# BottomBoard.net
KiCad netlist of a schematic drawn in Altium Designer
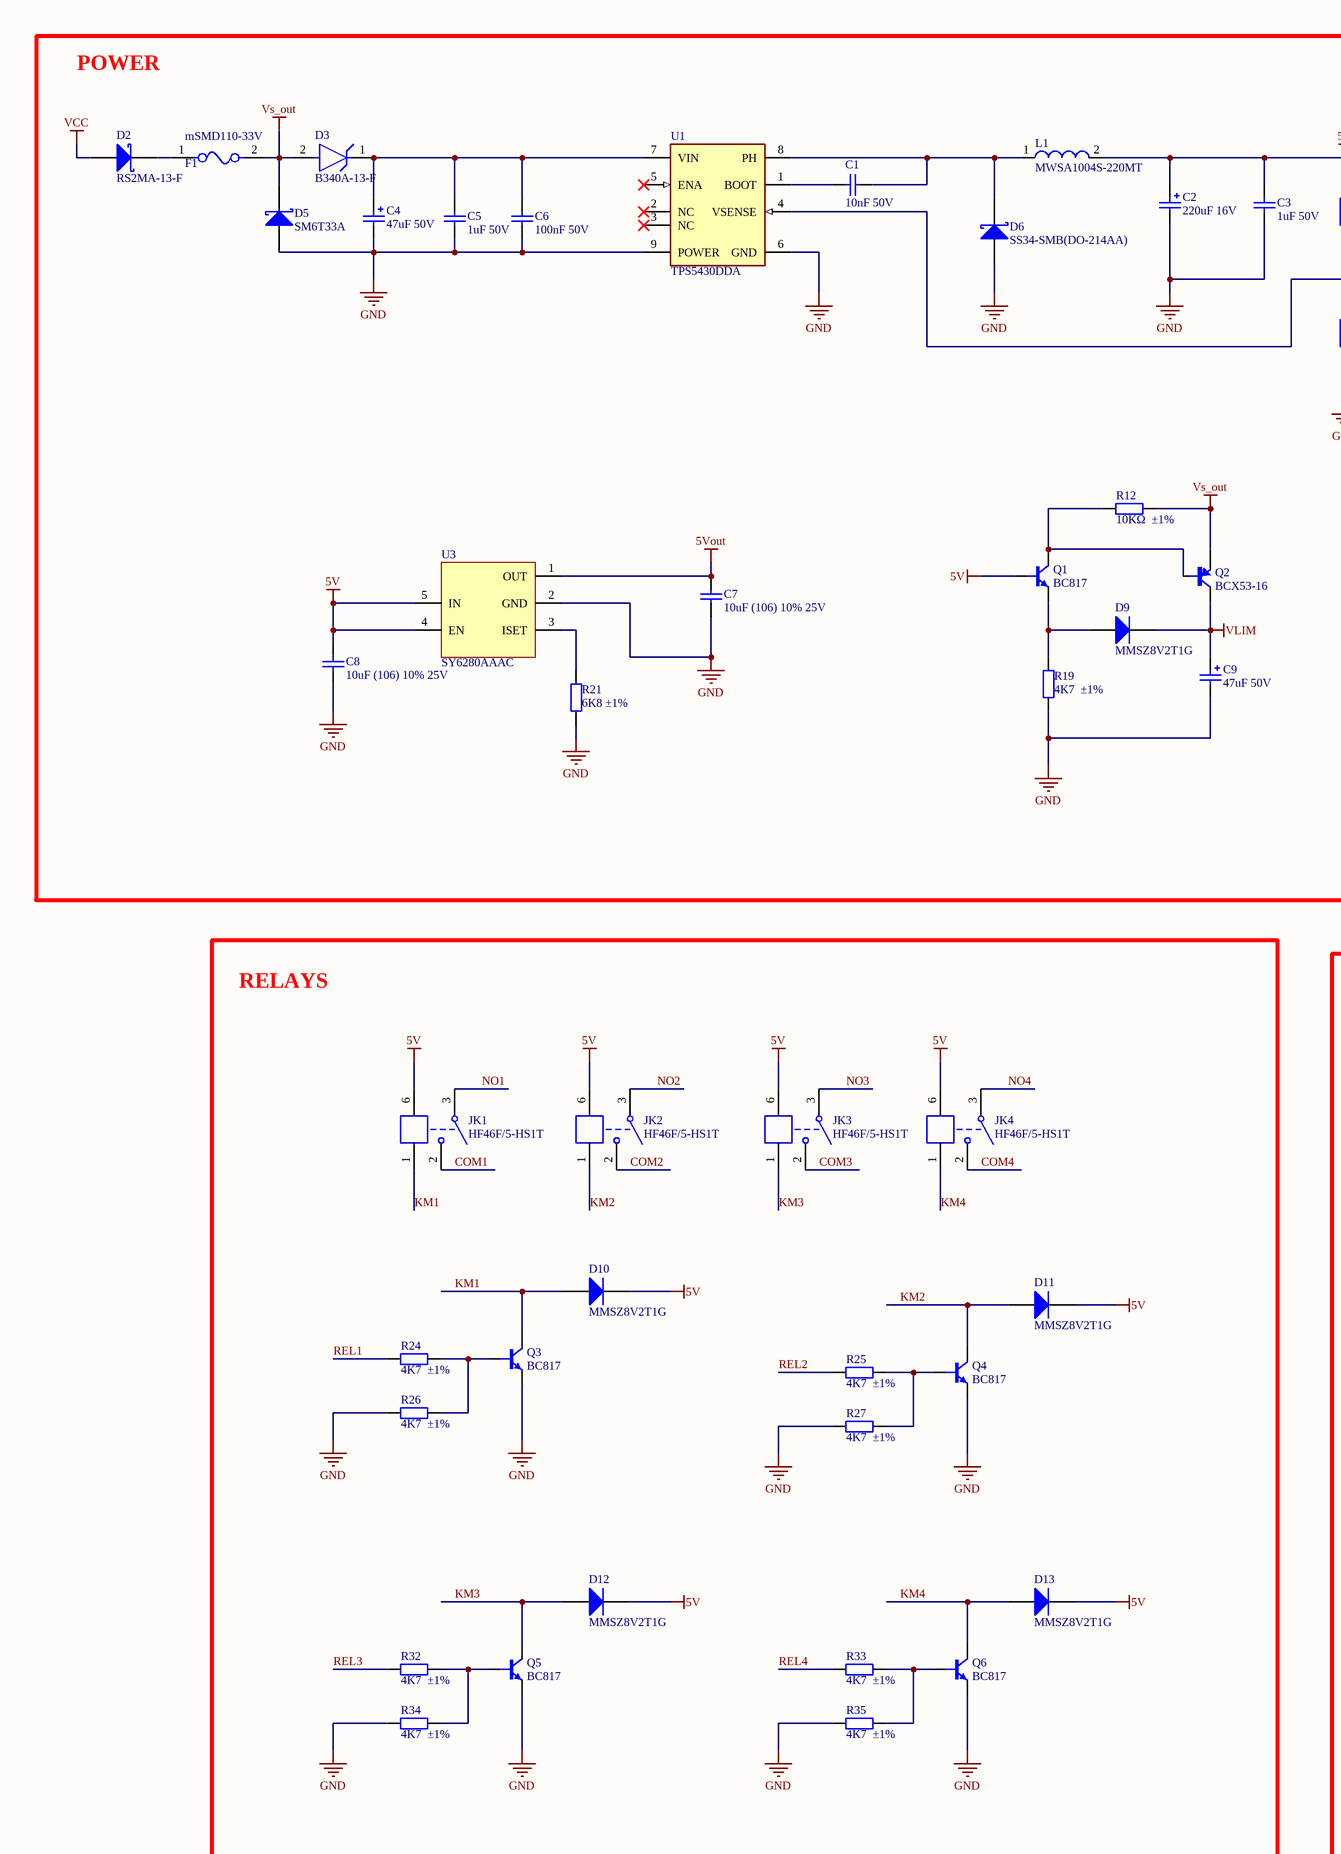
[diagram p0: BottomBoard.SchDoc, left]
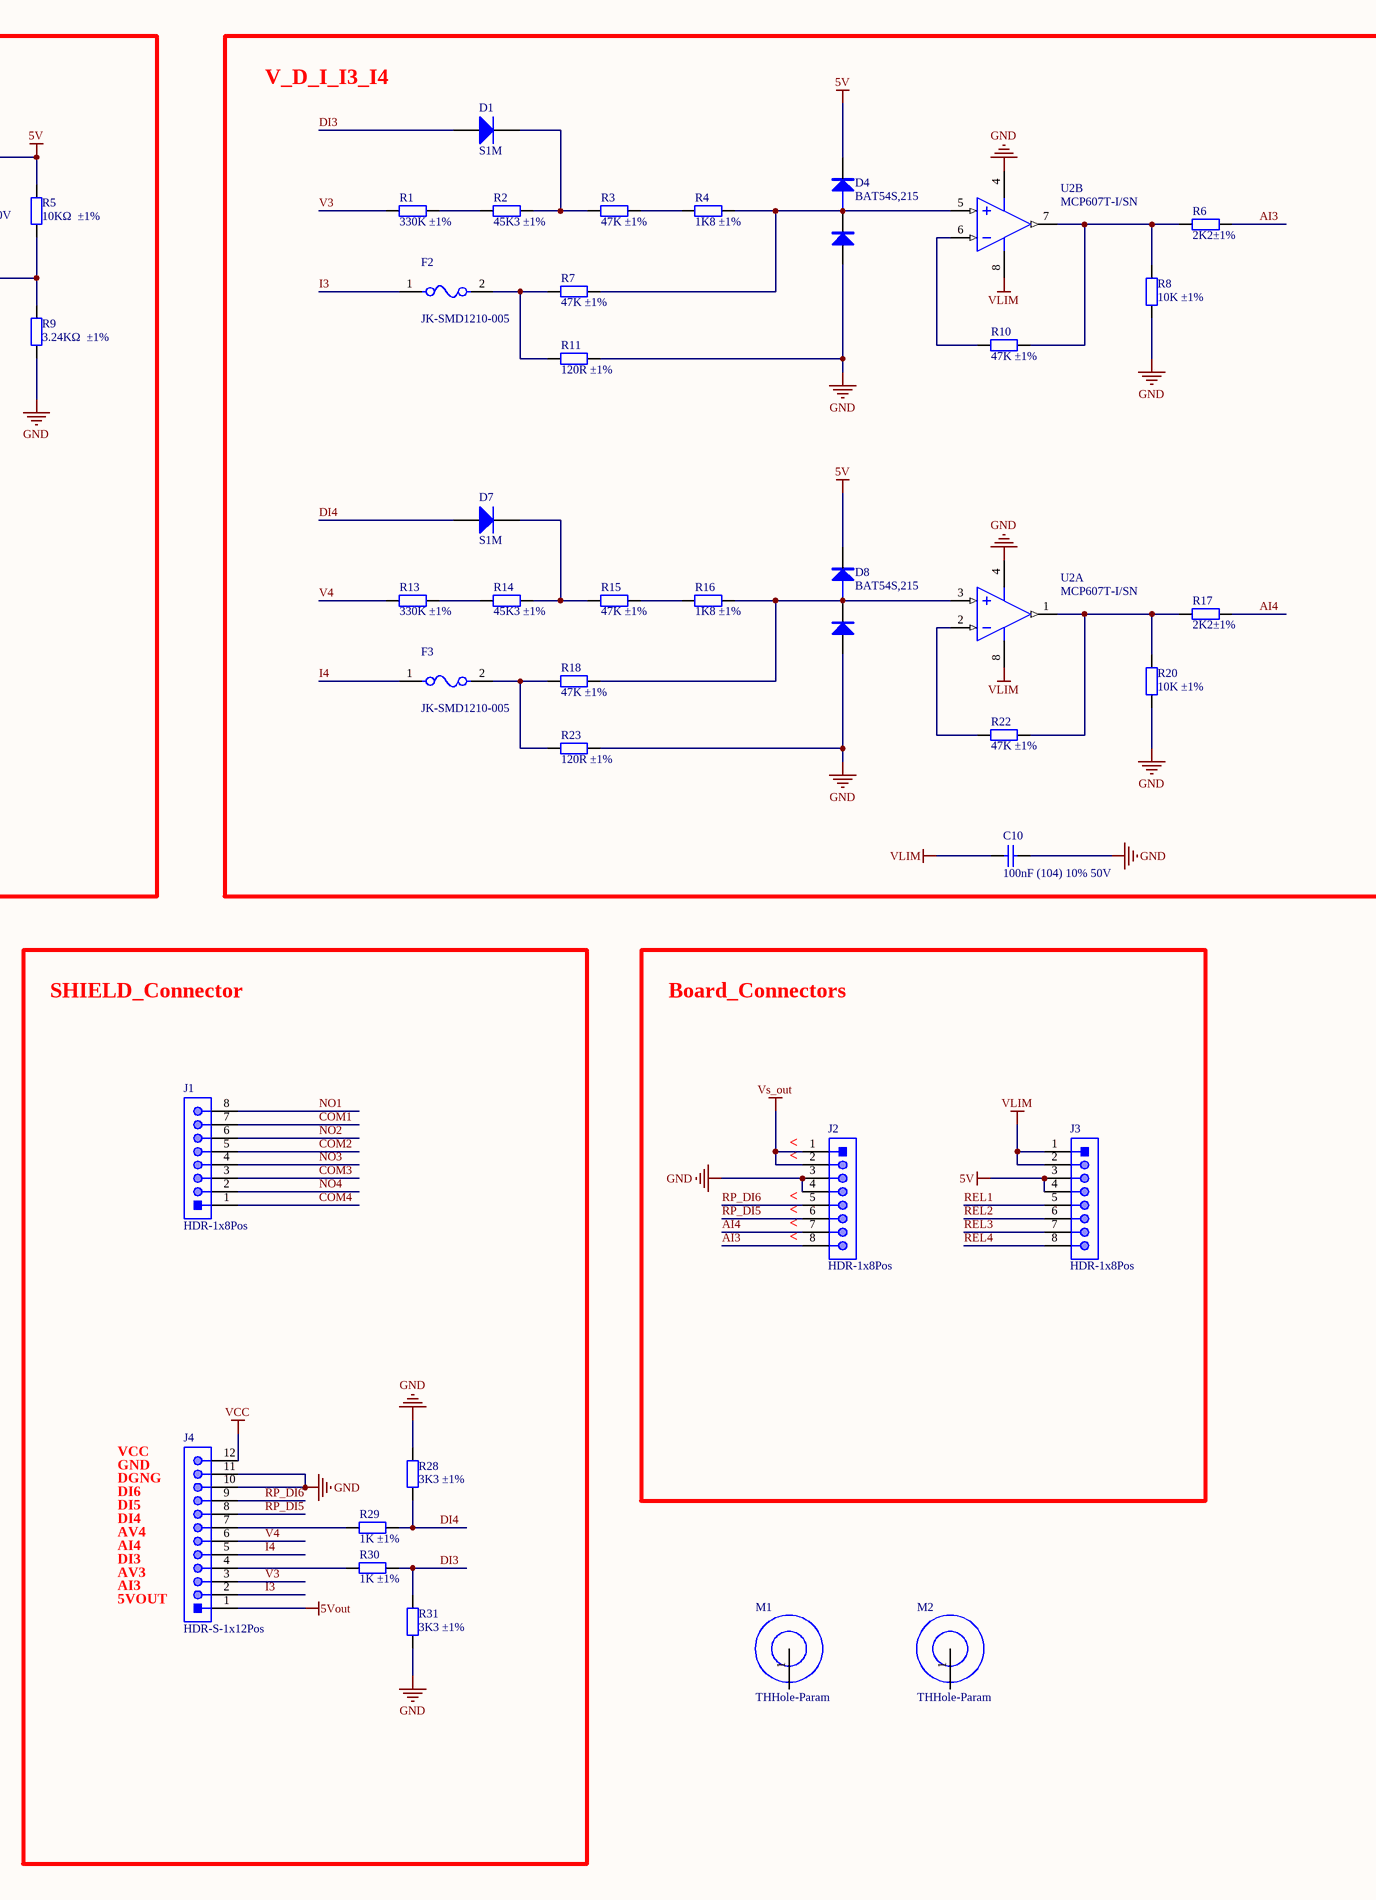
[diagram p1: BottomBoard.SchDoc, right]

(export (version "E")
  (design (tool "Eeschema 10.0.6"))
  (components
    (comp (ref "C1")
      (value "10nF 50V")
      (footprint "0402_C")
      (description "贴片电容")
      (libsource (lib "aiskylab-02Cap-01Ceramics") (part "0402 100nF (104) 10% 16V"))
    )
    (comp (ref "C2")
      (value "220uF 16V")
      (footprint "SMD-EC-F8")
      (description "贴片铝电解电容 8x10.2mm")
      (libsource (lib "aiskylab-02Cap-02Tan_SMT") (part "Alu-220uF 25V-F8"))
    )
    (comp (ref "C3")
      (value "1uF 50V")
      (footprint "0603_C")
      (description "贴片电容")
      (libsource (lib "aiskylab-02Cap-01Ceramics") (part "0603 10uF (106) 10% 10V"))
    )
    (comp (ref "C4")
      (value "47uF 50V")
      (footprint "SMD-EC-F6.3")
      (description "贴片铝电解电容")
      (libsource (lib "aiskylab-02Cap-02Tan_SMT") (part "Alu-100uF 25V"))
    )
    (comp (ref "C5")
      (value "1uF 50V")
      (footprint "0603_C")
      (description "贴片电容")
      (libsource (lib "aiskylab-02Cap-01Ceramics") (part "0603 10uF (106) 10% 10V"))
    )
    (comp (ref "C6")
      (value "100nF 50V")
      (footprint "0402_C")
      (description "贴片电容")
      (libsource (lib "aiskylab-02Cap-01Ceramics") (part "0402 100nF (104) 10% 16V"))
    )
    (comp (ref "C7")
      (value "10uF (106) 10% 25V")
      (footprint "0603_C")
      (description "贴片电容")
      (libsource (lib "aiskylab-02Cap-01Ceramics") (part "0603 10uF (106) 10% 10V"))
    )
    (comp (ref "C8")
      (value "10uF (106) 10% 25V")
      (footprint "0603_C")
      (description "贴片电容")
      (libsource (lib "aiskylab-02Cap-01Ceramics") (part "0603 10uF (106) 10% 10V"))
    )
    (comp (ref "C9")
      (value "47uF 50V")
      (footprint "SMD-EC-F6.3")
      (description "贴片铝电解电容")
      (libsource (lib "aiskylab-02Cap-02Tan_SMT") (part "Alu-100uF 25V"))
    )
    (comp (ref "C10")
      (value "100nF (104) 10% 50V")
      (footprint "0402_C")
      (description "贴片电容")
      (libsource (lib "aiskylab-02Cap-01Ceramics") (part "0402 100nF (104) 10% 16V"))
    )
    (comp (ref "D1")
      (value "S1M")
      (footprint "DO-214AC")
      (description "肖特基二极管")
      (fields (field (name "MANUFACTURER") "MCC") (field (name "MANUFACTURER PART NUMBER") "B5817WS-TP"))
      (libsource (lib "aiskylab-04Dio-1K") (part "B5817WS-TP"))
    )
    (comp (ref "D2")
      (value "RS2MA-13-F")
      (footprint "DIOD-SMA-1K")
      (description "B230A-13-F,SCHOTTKY RECTIFIER")
      (fields (field (name "MANUFACTURER") "Diodes") (field (name "MANUFACTURER PART NUMBER") "B230A-13-F"))
      (libsource (lib "aiskylab-04Dio-1K") (part "B230A-13-F"))
    )
    (comp (ref "D3")
      (value "B340A-13-F")
      (footprint "DO-214AC")
      (fields
        (field (name "PARTNUMBER") "SMAJ16A-E3/61")
        (field (name "MANUFACTURER") "Vishay Semiconductor")
      )
      (libsource (lib "aiskylab-04Dio-1K") (part "SMAJ16A"))
    )
    (comp (ref "D4")
      (value "BAT54S,215")
      (footprint "SOT-23-3")
      (description "肖特基二极管")
      (libsource (lib "Schlib1") (part "BAT54S,215"))
    )
    (comp (ref "D5")
      (value "SM6T33A")
      (footprint "DO-214AA")
      (description "3A 肖特基二极管")
      (libsource (lib "aiskylab-04Dio-1K") (part "SS34-SMB"))
    )
    (comp (ref "D6")
      (value "SS34-SMB(DO-214AA)")
      (footprint "DO-214AA")
      (description "3A 肖特基二极管")
      (libsource (lib "aiskylab-04Dio-1K") (part "SS34-SMB"))
    )
    (comp (ref "D7")
      (value "S1M")
      (footprint "DO-214AC")
      (description "肖特基二极管")
      (fields (field (name "MANUFACTURER") "MCC") (field (name "MANUFACTURER PART NUMBER") "B5817WS-TP"))
      (libsource (lib "aiskylab-04Dio-1K") (part "B5817WS-TP"))
    )
    (comp (ref "D8")
      (value "BAT54S,215")
      (footprint "SOT-23-3")
      (description "肖特基二极管")
      (libsource (lib "Schlib1") (part "BAT54S,215"))
    )
    (comp (ref "D9")
      (value "MMSZ8V2T1G")
      (footprint "SOD-123-1A")
      (description "Fast Switching Diode, 100 V, 0.15 A, -65 to 150 degC, 2-Pin?SOD123, RoHS, Tape and Reel")
      (fields (field (name "MANUFACTURER") "DiodesIncorporated"))
      (libsource (lib "aiskylab-04Dio-1K") (part "1N4148W-7-F"))
    )
    (comp (ref "D10")
      (value "MMSZ8V2T1G")
      (footprint "SOD-123-1A")
      (description "Fast Switching Diode, 100 V, 0.15 A, -65 to 150 degC, 2-Pin?SOD123, RoHS, Tape and Reel")
      (fields (field (name "MANUFACTURER") "DiodesIncorporated"))
      (libsource (lib "aiskylab-04Dio-1K") (part "1N4148W-7-F"))
    )
    (comp (ref "D11")
      (value "MMSZ8V2T1G")
      (footprint "SOD-123-1A")
      (description "Fast Switching Diode, 100 V, 0.15 A, -65 to 150 degC, 2-Pin?SOD123, RoHS, Tape and Reel")
      (fields (field (name "MANUFACTURER") "DiodesIncorporated"))
      (libsource (lib "aiskylab-04Dio-1K") (part "1N4148W-7-F"))
    )
    (comp (ref "D12")
      (value "MMSZ8V2T1G")
      (footprint "SOD-123-1A")
      (description "Fast Switching Diode, 100 V, 0.15 A, -65 to 150 degC, 2-Pin?SOD123, RoHS, Tape and Reel")
      (fields (field (name "MANUFACTURER") "DiodesIncorporated"))
      (libsource (lib "aiskylab-04Dio-1K") (part "1N4148W-7-F"))
    )
    (comp (ref "D13")
      (value "MMSZ8V2T1G")
      (footprint "SOD-123-1A")
      (description "Fast Switching Diode, 100 V, 0.15 A, -65 to 150 degC, 2-Pin?SOD123, RoHS, Tape and Reel")
      (fields (field (name "MANUFACTURER") "DiodesIncorporated"))
      (libsource (lib "aiskylab-04Dio-1K") (part "1N4148W-7-F"))
    )
    (comp (ref "F1")
      (value "mSMD110-33V")
      (footprint "1812_R")
      (description "贴片保险，自恢复")
      (libsource (lib "aiskylab-09CirProtect") (part "Fuse 2A 0805"))
    )
    (comp (ref "F2")
      (value "JK-SMD1210-005")
      (footprint "1210_R")
      (description "贴片保险，自恢复")
      (libsource (lib "aiskylab-09CirProtect") (part "Fuse 2A 0805"))
    )
    (comp (ref "F3")
      (value "JK-SMD1210-005")
      (footprint "1210_R")
      (description "贴片保险，自恢复")
      (libsource (lib "aiskylab-09CirProtect") (part "Fuse 2A 0805"))
    )
    (comp (ref "J1")
      (value "HDR-1x8Pos")
      (footprint "KF2EDG3.50-8H")
      (description "2.54mm 排针")
      (libsource (lib "aiskylab-14Connectors-17HeadersAndWireHousing") (part "HDR-1x8Pos"))
    )
    (comp (ref "J2")
      (value "HDR-1x8Pos")
      (footprint "Pin Header 1x8 TH Pitch 2.54mm")
      (description "2.54mm 排针")
      (libsource (lib "") (part "HDR-1x8Pos_1"))
    )
    (comp (ref "J3")
      (value "HDR-1x8Pos")
      (footprint "Pin Header 1x8 TH Pitch 2.54mm")
      (description "2.54mm 排针")
      (libsource (lib "") (part "HDR-1x8Pos_1"))
    )
    (comp (ref "J4")
      (value "HDR-S-1x12Pos")
      (footprint "KF2EDGK-2.54-WI-12P")
      (description "2.54mm 排座")
      (libsource (lib "aiskylab-14Connectors-17HeadersAndWireHousing") (part "HDR-S-1x12Pos"))
    )
    (comp (ref "JK1")
      (value "HF46F/5-HS1T")
      (footprint "RELAY-TH_HF46F-5-HS1T")
      (description "5V一组常开")
      (libsource (lib "Schlib1") (part "HF46F/5-HS1T"))
    )
    (comp (ref "JK2")
      (value "HF46F/5-HS1T")
      (footprint "RELAY-TH_HF46F-5-HS1T")
      (description "5V一组常开")
      (libsource (lib "Schlib1") (part "HF46F/5-HS1T"))
    )
    (comp (ref "JK3")
      (value "HF46F/5-HS1T")
      (footprint "RELAY-TH_HF46F-5-HS1T")
      (description "5V一组常开")
      (libsource (lib "Schlib1") (part "HF46F/5-HS1T"))
    )
    (comp (ref "JK4")
      (value "HF46F/5-HS1T")
      (footprint "RELAY-TH_HF46F-5-HS1T")
      (description "5V一组常开")
      (libsource (lib "Schlib1") (part "HF46F/5-HS1T"))
    )
    (comp (ref "L1")
      (value "MWSA1004S-220MT")
      (footprint "MWSA1004S")
      (description "功率电感")
      (fields (field (name "MANUFACTURERPARTNUMBER") "MWSA1004S-470MT"))
      (libsource (lib "aiskylab-03Indu") (part "MWSA1004S-220MT"))
    )
    (comp (ref "M1")
      (value "THHole-Param")
      (footprint "MTG300_600")
      (description "金属化可接地固定孔")
      (libsource (lib "aiskylab-14Connectors-20TestAndMechenical") (part "MHole-1"))
    )
    (comp (ref "M2")
      (value "THHole-Param")
      (footprint "MTG300_600")
      (description "金属化可接地固定孔")
      (libsource (lib "aiskylab-14Connectors-20TestAndMechenical") (part "MHole-1"))
    )
    (comp (ref "Q1")
      (value "BC817")
      (footprint "SOT-23-3")
      (description "NPN贴片三极管")
      (libsource (lib "aiskylab-05Transistors") (part "BC817"))
    )
    (comp (ref "Q2")
      (value "BCX53-16")
      (footprint "SOT89_M")
      (description "PNP贴片三极管")
      (libsource (lib "aiskylab-05Transistors") (part "BCX53-16"))
    )
    (comp (ref "Q3")
      (value "BC817")
      (footprint "SOT-23-3")
      (description "NPN贴片三极管")
      (libsource (lib "aiskylab-05Transistors") (part "BC817"))
    )
    (comp (ref "Q4")
      (value "BC817")
      (footprint "SOT-23-3")
      (description "NPN贴片三极管")
      (libsource (lib "aiskylab-05Transistors") (part "BC817"))
    )
    (comp (ref "Q5")
      (value "BC817")
      (footprint "SOT-23-3")
      (description "NPN贴片三极管")
      (libsource (lib "aiskylab-05Transistors") (part "BC817"))
    )
    (comp (ref "Q6")
      (value "BC817")
      (footprint "SOT-23-3")
      (description "NPN贴片三极管")
      (libsource (lib "aiskylab-05Transistors") (part "BC817"))
    )
    (comp (ref "R1")
      (value "330K ±1%")
      (footprint "0402_R")
      (description "贴片电阻")
      (libsource (lib "") (part "0402 1.2KΩ (1201) 1%_1"))
    )
    (comp (ref "R2")
      (value "45K3 ±1%")
      (footprint "0402_R")
      (description "贴片电阻")
      (libsource (lib "") (part "0402 1.2KΩ (1201) 1%_1"))
    )
    (comp (ref "R3")
      (value "47K ±1%")
      (footprint "0402_R")
      (description "贴片电阻")
      (libsource (lib "") (part "0402 1.2KΩ (1201) 1%_1"))
    )
    (comp (ref "R4")
      (value "1K8 ±1%")
      (footprint "0402_R")
      (description "贴片电阻")
      (libsource (lib "") (part "0402 1.2KΩ (1201) 1%_1"))
    )
    (comp (ref "R5")
      (value "10KΩ  ±1%")
      (footprint "0402_R")
      (description "贴片电阻")
      (libsource (lib "") (part "0402 1.2KΩ (1201) 1%_3"))
    )
    (comp (ref "R6")
      (value "2K2±1%")
      (footprint "0402_R")
      (description "贴片电阻")
      (libsource (lib "aiskylab-01Resistors") (part "0402 1.2KΩ (1201) 1%"))
    )
    (comp (ref "R7")
      (value "47K ±1%")
      (footprint "0402_R")
      (description "贴片电阻")
      (libsource (lib "") (part "0402 1.2KΩ (1201) 1%_1"))
    )
    (comp (ref "R8")
      (value "10K ±1%")
      (footprint "0402_R")
      (description "贴片电阻")
      (libsource (lib "") (part "0402 1.2KΩ (1201) 1%_2"))
    )
    (comp (ref "R9")
      (value "3.24KΩ  ±1%")
      (footprint "0402_R")
      (description "贴片电阻")
      (libsource (lib "") (part "0402 1.2KΩ (1201) 1%_3"))
    )
    (comp (ref "R10")
      (value "47K ±1%")
      (footprint "0402_R")
      (description "贴片电阻")
      (libsource (lib "") (part "0402 1.2KΩ (1201) 1%_1"))
    )
    (comp (ref "R11")
      (value "120R ±1%")
      (footprint "RS 1/4W-V3")
      (description "贴片电阻")
      (libsource (lib "") (part "0402 1.2KΩ (1201) 1%_1"))
    )
    (comp (ref "R12")
      (value "10KΩ  ±1%")
      (footprint "0402_R")
      (description "贴片电阻")
      (libsource (lib "") (part "0402 1.2KΩ (1201) 1%_1"))
    )
    (comp (ref "R13")
      (value "330K ±1%")
      (footprint "0402_R")
      (description "贴片电阻")
      (libsource (lib "") (part "0402 1.2KΩ (1201) 1%_1"))
    )
    (comp (ref "R14")
      (value "45K3 ±1%")
      (footprint "0402_R")
      (description "贴片电阻")
      (libsource (lib "") (part "0402 1.2KΩ (1201) 1%_1"))
    )
    (comp (ref "R15")
      (value "47K ±1%")
      (footprint "0402_R")
      (description "贴片电阻")
      (libsource (lib "") (part "0402 1.2KΩ (1201) 1%_1"))
    )
    (comp (ref "R16")
      (value "1K8 ±1%")
      (footprint "0402_R")
      (description "贴片电阻")
      (libsource (lib "") (part "0402 1.2KΩ (1201) 1%_1"))
    )
    (comp (ref "R17")
      (value "2K2±1%")
      (footprint "0402_R")
      (description "贴片电阻")
      (libsource (lib "aiskylab-01Resistors") (part "0402 1.2KΩ (1201) 1%"))
    )
    (comp (ref "R18")
      (value "47K ±1%")
      (footprint "0402_R")
      (description "贴片电阻")
      (libsource (lib "") (part "0402 1.2KΩ (1201) 1%_1"))
    )
    (comp (ref "R19")
      (value "4K7  ±1%")
      (footprint "0402_R")
      (description "贴片电阻")
      (libsource (lib "") (part "0402 1.2KΩ (1201) 1%_2"))
    )
    (comp (ref "R20")
      (value "10K ±1%")
      (footprint "0402_R")
      (description "贴片电阻")
      (libsource (lib "") (part "0402 1.2KΩ (1201) 1%_2"))
    )
    (comp (ref "R21")
      (value "6K8 ±1%")
      (footprint "0402_R")
      (description "贴片电阻")
      (libsource (lib "aiskylab-01Resistors") (part "0402 1.2KΩ (1201) 1%"))
    )
    (comp (ref "R22")
      (value "47K ±1%")
      (footprint "0402_R")
      (description "贴片电阻")
      (libsource (lib "") (part "0402 1.2KΩ (1201) 1%_1"))
    )
    (comp (ref "R23")
      (value "120R ±1%")
      (footprint "RS 1/4W-V3")
      (description "贴片电阻")
      (libsource (lib "") (part "0402 1.2KΩ (1201) 1%_1"))
    )
    (comp (ref "R24")
      (value "4K7  ±1%")
      (footprint "0402_R")
      (description "贴片电阻")
      (libsource (lib "aiskylab-01Resistors") (part "0402 1.2KΩ (1201) 1%"))
    )
    (comp (ref "R25")
      (value "4K7  ±1%")
      (footprint "0402_R")
      (description "贴片电阻")
      (libsource (lib "aiskylab-01Resistors") (part "0402 1.2KΩ (1201) 1%"))
    )
    (comp (ref "R26")
      (value "4K7  ±1%")
      (footprint "0402_R")
      (description "贴片电阻")
      (libsource (lib "aiskylab-01Resistors") (part "0402 1.2KΩ (1201) 1%"))
    )
    (comp (ref "R27")
      (value "4K7  ±1%")
      (footprint "0402_R")
      (description "贴片电阻")
      (libsource (lib "aiskylab-01Resistors") (part "0402 1.2KΩ (1201) 1%"))
    )
    (comp (ref "R28")
      (value "3K3 ±1%")
      (footprint "0402_R")
      (description "贴片电阻")
      (libsource (lib "") (part "0402 1.2KΩ (1201) 1%_2"))
    )
    (comp (ref "R29")
      (value "1K ±1%")
      (footprint "0402_R")
      (description "贴片电阻")
      (libsource (lib "aiskylab-01Resistors") (part "0402 1.2KΩ (1201) 1%"))
    )
    (comp (ref "R30")
      (value "1K ±1%")
      (footprint "0402_R")
      (description "贴片电阻")
      (libsource (lib "aiskylab-01Resistors") (part "0402 1.2KΩ (1201) 1%"))
    )
    (comp (ref "R31")
      (value "3K3 ±1%")
      (footprint "0402_R")
      (description "贴片电阻")
      (libsource (lib "") (part "0402 1.2KΩ (1201) 1%_3"))
    )
    (comp (ref "R32")
      (value "4K7  ±1%")
      (footprint "0402_R")
      (description "贴片电阻")
      (libsource (lib "aiskylab-01Resistors") (part "0402 1.2KΩ (1201) 1%"))
    )
    (comp (ref "R33")
      (value "4K7  ±1%")
      (footprint "0402_R")
      (description "贴片电阻")
      (libsource (lib "aiskylab-01Resistors") (part "0402 1.2KΩ (1201) 1%"))
    )
    (comp (ref "R34")
      (value "4K7  ±1%")
      (footprint "0402_R")
      (description "贴片电阻")
      (libsource (lib "aiskylab-01Resistors") (part "0402 1.2KΩ (1201) 1%"))
    )
    (comp (ref "R35")
      (value "4K7  ±1%")
      (footprint "0402_R")
      (description "贴片电阻")
      (libsource (lib "aiskylab-01Resistors") (part "0402 1.2KΩ (1201) 1%"))
    )
    (comp (ref "U1")
      (value "TPS5430DDA")
      (footprint "DDA0008J_L")
      (description "5.5V to 36V Input, 3A, 500kHz Step-Down Converter 8-SO PowerPAD 0 to 0")
      (fields (field (name "MANUFACTURER") "Texas Instruments"))
      (libsource (lib "aiskylab-06IC-04PWR") (part "TPS5430DDA"))
    )
    (comp (ref "U2")
      (value "MCP607T-I/SN")
      (footprint "D0008A_L")
      (libsource (lib "aiskylab-06IC-01Linear") (part "TI-LM358DR"))
    )
    (comp (ref "U3")
      (value "SY6280AAAC")
      (footprint "SOT-23-5")
      (description "USB电子开关，电流保护")
      (libsource (lib "Schlib1") (part "SY6280AAAC"))
    )
  )
  (nets
    (net (code "1") (name "/AI3") (class "Default")
      (node (ref "J2") (pin "8") (pinfunction "8_8") (pintype "passive"))
      (node (ref "R6") (pin "2") (pinfunction "2_2") (pintype "passive"))
    )
    (net (code "2") (name "/AI4") (class "Default")
      (node (ref "J2") (pin "7") (pinfunction "7_7") (pintype "passive"))
      (node (ref "R17") (pin "2") (pinfunction "2_2") (pintype "passive"))
    )
    (net (code "3") (name "/COM1") (class "Default")
      (node (ref "J1") (pin "7") (pinfunction "7_7") (pintype "passive"))
      (node (ref "JK1") (pin "2") (pinfunction "2_2") (pintype "passive"))
    )
    (net (code "4") (name "/COM2") (class "Default")
      (node (ref "J1") (pin "5") (pinfunction "5_5") (pintype "passive"))
      (node (ref "JK2") (pin "2") (pinfunction "2_2") (pintype "passive"))
    )
    (net (code "5") (name "/COM3") (class "Default")
      (node (ref "J1") (pin "3") (pinfunction "3_3") (pintype "passive"))
      (node (ref "JK3") (pin "2") (pinfunction "2_2") (pintype "passive"))
    )
    (net (code "6") (name "/COM4") (class "Default")
      (node (ref "J1") (pin "1") (pinfunction "1_1") (pintype "passive"))
      (node (ref "JK4") (pin "2") (pinfunction "2_2") (pintype "passive"))
    )
    (net (code "7") (name "/DI3") (class "Default")
      (node (ref "D1") (pin "2") (pinfunction "A_2") (pintype "passive"))
      (node (ref "R30") (pin "2") (pinfunction "2_2") (pintype "passive"))
      (node (ref "R31") (pin "2") (pinfunction "2_2") (pintype "passive"))
    )
    (net (code "8") (name "/DI4") (class "Default")
      (node (ref "D7") (pin "2") (pinfunction "A_2") (pintype "passive"))
      (node (ref "R28") (pin "2") (pinfunction "2_2") (pintype "passive"))
      (node (ref "R29") (pin "2") (pinfunction "2_2") (pintype "passive"))
    )
    (net (code "9") (name "/I3") (class "Default")
      (node (ref "F2") (pin "1") (pinfunction "1_1") (pintype "passive"))
      (node (ref "J4") (pin "2") (pinfunction "2_2") (pintype "passive"))
    )
    (net (code "10") (name "/I4") (class "Default")
      (node (ref "F3") (pin "1") (pinfunction "1_1") (pintype "passive"))
      (node (ref "J4") (pin "5") (pinfunction "5_5") (pintype "passive"))
    )
    (net (code "11") (name "/KM1") (class "Default")
      (node (ref "D10") (pin "2") (pinfunction "A_2") (pintype "passive"))
      (node (ref "JK1") (pin "1") (pinfunction "1_1") (pintype "passive"))
      (node (ref "Q3") (pin "3") (pinfunction "C_3") (pintype "passive"))
    )
    (net (code "12") (name "/KM2") (class "Default")
      (node (ref "D11") (pin "2") (pinfunction "A_2") (pintype "passive"))
      (node (ref "JK2") (pin "1") (pinfunction "1_1") (pintype "passive"))
      (node (ref "Q4") (pin "3") (pinfunction "C_3") (pintype "passive"))
    )
    (net (code "13") (name "/KM3") (class "Default")
      (node (ref "D12") (pin "2") (pinfunction "A_2") (pintype "passive"))
      (node (ref "JK3") (pin "1") (pinfunction "1_1") (pintype "passive"))
      (node (ref "Q5") (pin "3") (pinfunction "C_3") (pintype "passive"))
    )
    (net (code "14") (name "/KM4") (class "Default")
      (node (ref "D13") (pin "2") (pinfunction "A_2") (pintype "passive"))
      (node (ref "JK4") (pin "1") (pinfunction "1_1") (pintype "passive"))
      (node (ref "Q6") (pin "3") (pinfunction "C_3") (pintype "passive"))
    )
    (net (code "15") (name "/NO1") (class "Default")
      (node (ref "J1") (pin "8") (pinfunction "8_8") (pintype "passive"))
      (node (ref "JK1") (pin "3") (pinfunction "3_3") (pintype "passive"))
    )
    (net (code "16") (name "/NO2") (class "Default")
      (node (ref "J1") (pin "6") (pinfunction "6_6") (pintype "passive"))
      (node (ref "JK2") (pin "3") (pinfunction "3_3") (pintype "passive"))
    )
    (net (code "17") (name "/NO3") (class "Default")
      (node (ref "J1") (pin "4") (pinfunction "4_4") (pintype "passive"))
      (node (ref "JK3") (pin "3") (pinfunction "3_3") (pintype "passive"))
    )
    (net (code "18") (name "/NO4") (class "Default")
      (node (ref "J1") (pin "2") (pinfunction "2_2") (pintype "passive"))
      (node (ref "JK4") (pin "3") (pinfunction "3_3") (pintype "passive"))
    )
    (net (code "19") (name "/REL1") (class "Default")
      (node (ref "J3") (pin "5") (pinfunction "5_5") (pintype "passive"))
      (node (ref "R24") (pin "1") (pinfunction "1_1") (pintype "passive"))
    )
    (net (code "20") (name "/REL2") (class "Default")
      (node (ref "J3") (pin "6") (pinfunction "6_6") (pintype "passive"))
      (node (ref "R25") (pin "1") (pinfunction "1_1") (pintype "passive"))
    )
    (net (code "21") (name "/REL3") (class "Default")
      (node (ref "J3") (pin "7") (pinfunction "7_7") (pintype "passive"))
      (node (ref "R32") (pin "1") (pinfunction "1_1") (pintype "passive"))
    )
    (net (code "22") (name "/REL4") (class "Default")
      (node (ref "J3") (pin "8") (pinfunction "8_8") (pintype "passive"))
      (node (ref "R33") (pin "1") (pinfunction "1_1") (pintype "passive"))
    )
    (net (code "23") (name "/RP_DI5") (class "Default")
      (node (ref "J2") (pin "6") (pinfunction "6_6") (pintype "passive"))
      (node (ref "J4") (pin "8") (pinfunction "8_8") (pintype "passive"))
    )
    (net (code "24") (name "/RP_DI6") (class "Default")
      (node (ref "J2") (pin "5") (pinfunction "5_5") (pintype "passive"))
      (node (ref "J4") (pin "9") (pinfunction "9_9") (pintype "passive"))
    )
    (net (code "25") (name "/V3") (class "Default")
      (node (ref "J4") (pin "3") (pinfunction "3_3") (pintype "passive"))
      (node (ref "R1") (pin "2") (pinfunction "2_2") (pintype "passive"))
    )
    (net (code "26") (name "/V4") (class "Default")
      (node (ref "J4") (pin "6") (pinfunction "6_6") (pintype "passive"))
      (node (ref "R13") (pin "2") (pinfunction "2_2") (pintype "passive"))
    )
    (net (code "27") (name "5V") (class "Default")
      (node (ref "C2") (pin "1") (pinfunction "1_1") (pintype "passive"))
      (node (ref "C3") (pin "2") (pinfunction "2_2") (pintype "passive"))
      (node (ref "C8") (pin "2") (pinfunction "2_2") (pintype "passive"))
      (node (ref "D10") (pin "1") (pinfunction "K_1") (pintype "passive"))
      (node (ref "D11") (pin "1") (pinfunction "K_1") (pintype "passive"))
      (node (ref "D12") (pin "1") (pinfunction "K_1") (pintype "passive"))
      (node (ref "D13") (pin "1") (pinfunction "K_1") (pintype "passive"))
      (node (ref "D4") (pin "2") (pinfunction "2_2") (pintype "passive"))
      (node (ref "D8") (pin "2") (pinfunction "2_2") (pintype "passive"))
      (node (ref "J3") (pin "3") (pinfunction "3_3") (pintype "passive"))
      (node (ref "J3") (pin "4") (pinfunction "4_4") (pintype "passive"))
      (node (ref "JK1") (pin "6") (pinfunction "6_6") (pintype "passive"))
      (node (ref "JK2") (pin "6") (pinfunction "6_6") (pintype "passive"))
      (node (ref "JK3") (pin "6") (pinfunction "6_6") (pintype "passive"))
      (node (ref "JK4") (pin "6") (pinfunction "6_6") (pintype "passive"))
      (node (ref "L1") (pin "2") (pinfunction "2_2") (pintype "passive"))
      (node (ref "Q1") (pin "1") (pinfunction "B_1") (pintype "passive"))
      (node (ref "R5") (pin "2") (pinfunction "2_2") (pintype "passive"))
      (node (ref "U3") (pin "4") (pinfunction "EN_4") (pintype "passive"))
      (node (ref "U3") (pin "5") (pinfunction "IN_5") (pintype "passive"))
    )
    (net (code "28") (name "5Vout") (class "Default")
      (node (ref "C7") (pin "2") (pinfunction "2_2") (pintype "passive"))
      (node (ref "J4") (pin "1") (pinfunction "1_1") (pintype "passive"))
      (node (ref "U3") (pin "1") (pinfunction "OUT_1") (pintype "passive"))
    )
    (net (code "29") (name "GND") (class "Default")
      (node (ref "C10") (pin "2") (pinfunction "2_2") (pintype "passive"))
      (node (ref "C2") (pin "2") (pinfunction "2_2") (pintype "passive"))
      (node (ref "C3") (pin "1") (pinfunction "1_1") (pintype "passive"))
      (node (ref "C4") (pin "2") (pinfunction "2_2") (pintype "passive"))
      (node (ref "C5") (pin "1") (pinfunction "1_1") (pintype "passive"))
      (node (ref "C6") (pin "1") (pinfunction "1_1") (pintype "passive"))
      (node (ref "C7") (pin "1") (pinfunction "1_1") (pintype "passive"))
      (node (ref "C8") (pin "1") (pinfunction "1_1") (pintype "passive"))
      (node (ref "C9") (pin "2") (pinfunction "2_2") (pintype "passive"))
      (node (ref "D4") (pin "1") (pinfunction "1_1") (pintype "passive"))
      (node (ref "D5") (pin "2") (pinfunction "A_2") (pintype "passive"))
      (node (ref "D6") (pin "2") (pinfunction "A_2") (pintype "passive"))
      (node (ref "D8") (pin "1") (pinfunction "1_1") (pintype "passive"))
      (node (ref "J2") (pin "3") (pinfunction "3_3") (pintype "passive"))
      (node (ref "J2") (pin "4") (pinfunction "4_4") (pintype "passive"))
      (node (ref "J4") (pin "10") (pinfunction "10_10") (pintype "passive"))
      (node (ref "J4") (pin "11") (pinfunction "11_11") (pintype "passive"))
      (node (ref "Q3") (pin "2") (pinfunction "E_2") (pintype "passive"))
      (node (ref "Q4") (pin "2") (pinfunction "E_2") (pintype "passive"))
      (node (ref "Q5") (pin "2") (pinfunction "E_2") (pintype "passive"))
      (node (ref "Q6") (pin "2") (pinfunction "E_2") (pintype "passive"))
      (node (ref "R11") (pin "1") (pinfunction "1_1") (pintype "passive"))
      (node (ref "R19") (pin "2") (pinfunction "2_2") (pintype "passive"))
      (node (ref "R20") (pin "2") (pinfunction "2_2") (pintype "passive"))
      (node (ref "R21") (pin "1") (pinfunction "1_1") (pintype "passive"))
      (node (ref "R23") (pin "1") (pinfunction "1_1") (pintype "passive"))
      (node (ref "R26") (pin "1") (pinfunction "1_1") (pintype "passive"))
      (node (ref "R27") (pin "1") (pinfunction "1_1") (pintype "passive"))
      (node (ref "R28") (pin "1") (pinfunction "1_1") (pintype "passive"))
      (node (ref "R31") (pin "1") (pinfunction "1_1") (pintype "passive"))
      (node (ref "R34") (pin "1") (pinfunction "1_1") (pintype "passive"))
      (node (ref "R35") (pin "1") (pinfunction "1_1") (pintype "passive"))
      (node (ref "R8") (pin "2") (pinfunction "2_2") (pintype "passive"))
      (node (ref "R9") (pin "1") (pinfunction "1_1") (pintype "passive"))
      (node (ref "U1") (pin "6") (pinfunction "GND_6") (pintype "power_in"))
      (node (ref "U1") (pin "9") (pinfunction "POWER_9") (pintype "power_in"))
      (node (ref "U2") (pin "4") (pinfunction "GND_4") (pintype "power_in"))
      (node (ref "U3") (pin "2") (pinfunction "GND_2") (pintype "passive"))
    )
    (net (code "30") (name "Net-(D1-K)") (class "Default")
      (node (ref "D1") (pin "1") (pinfunction "K_1") (pintype "passive"))
      (node (ref "R2") (pin "1") (pinfunction "1_1") (pintype "passive"))
      (node (ref "R3") (pin "2") (pinfunction "2_2") (pintype "passive"))
    )
    (net (code "31") (name "Net-(D2-K)") (class "Default")
      (node (ref "D2") (pin "1") (pinfunction "K_1") (pintype "passive"))
      (node (ref "F1") (pin "1") (pinfunction "1_1") (pintype "passive"))
    )
    (net (code "32") (name "Net-(D3-C)") (class "Default")
      (node (ref "C4") (pin "1") (pinfunction "1_1") (pintype "passive"))
      (node (ref "C5") (pin "2") (pinfunction "2_2") (pintype "passive"))
      (node (ref "C6") (pin "2") (pinfunction "2_2") (pintype "passive"))
      (node (ref "D3") (pin "1") (pinfunction "C_1") (pintype "passive"))
      (node (ref "U1") (pin "7") (pinfunction "VIN_7") (pintype "power_in"))
    )
    (net (code "33") (name "Net-(D6-K)") (class "Default")
      (node (ref "C1") (pin "1") (pinfunction "1_1") (pintype "passive"))
      (node (ref "D6") (pin "1") (pinfunction "K_1") (pintype "passive"))
      (node (ref "L1") (pin "1") (pinfunction "1_1") (pintype "passive"))
      (node (ref "U1") (pin "8") (pinfunction "PH_8") (pintype "power_in"))
    )
    (net (code "34") (name "Net-(D7-K)") (class "Default")
      (node (ref "D7") (pin "1") (pinfunction "K_1") (pintype "passive"))
      (node (ref "R14") (pin "1") (pinfunction "1_1") (pintype "passive"))
      (node (ref "R15") (pin "2") (pinfunction "2_2") (pintype "passive"))
    )
    (net (code "35") (name "Net-(D9-A)") (class "Default")
      (node (ref "D9") (pin "2") (pinfunction "A_2") (pintype "passive"))
      (node (ref "Q1") (pin "2") (pinfunction "E_2") (pintype "passive"))
      (node (ref "R19") (pin "1") (pinfunction "1_1") (pintype "passive"))
    )
    (net (code "36") (name "Net-(F2-Pad2)") (class "Default")
      (node (ref "F2") (pin "2") (pinfunction "2_2") (pintype "passive"))
      (node (ref "R11") (pin "2") (pinfunction "2_2") (pintype "passive"))
      (node (ref "R7") (pin "2") (pinfunction "2_2") (pintype "passive"))
    )
    (net (code "37") (name "Net-(F3-Pad2)") (class "Default")
      (node (ref "F3") (pin "2") (pinfunction "2_2") (pintype "passive"))
      (node (ref "R18") (pin "2") (pinfunction "2_2") (pintype "passive"))
      (node (ref "R23") (pin "2") (pinfunction "2_2") (pintype "passive"))
    )
    (net (code "38") (name "Net-(J4-Pad4)") (class "Default")
      (node (ref "J4") (pin "4") (pinfunction "4_4") (pintype "passive"))
      (node (ref "R30") (pin "1") (pinfunction "1_1") (pintype "passive"))
    )
    (net (code "39") (name "Net-(J4-Pad7)") (class "Default")
      (node (ref "J4") (pin "7") (pinfunction "7_7") (pintype "passive"))
      (node (ref "R29") (pin "1") (pinfunction "1_1") (pintype "passive"))
    )
    (net (code "40") (name "Net-(Q1-C)") (class "Default")
      (node (ref "Q1") (pin "3") (pinfunction "C_3") (pintype "passive"))
      (node (ref "Q2") (pin "1") (pinfunction "B_1") (pintype "passive"))
      (node (ref "R12") (pin "2") (pinfunction "2_2") (pintype "passive"))
    )
    (net (code "41") (name "Net-(Q3-B)") (class "Default")
      (node (ref "Q3") (pin "1") (pinfunction "B_1") (pintype "passive"))
      (node (ref "R24") (pin "2") (pinfunction "2_2") (pintype "passive"))
      (node (ref "R26") (pin "2") (pinfunction "2_2") (pintype "passive"))
    )
    (net (code "42") (name "Net-(Q4-B)") (class "Default")
      (node (ref "Q4") (pin "1") (pinfunction "B_1") (pintype "passive"))
      (node (ref "R25") (pin "2") (pinfunction "2_2") (pintype "passive"))
      (node (ref "R27") (pin "2") (pinfunction "2_2") (pintype "passive"))
    )
    (net (code "43") (name "Net-(Q5-B)") (class "Default")
      (node (ref "Q5") (pin "1") (pinfunction "B_1") (pintype "passive"))
      (node (ref "R32") (pin "2") (pinfunction "2_2") (pintype "passive"))
      (node (ref "R34") (pin "2") (pinfunction "2_2") (pintype "passive"))
    )
    (net (code "44") (name "Net-(Q6-B)") (class "Default")
      (node (ref "Q6") (pin "1") (pinfunction "B_1") (pintype "passive"))
      (node (ref "R33") (pin "2") (pinfunction "2_2") (pintype "passive"))
      (node (ref "R35") (pin "2") (pinfunction "2_2") (pintype "passive"))
    )
    (net (code "45") (name "Net-(R1-Pad1)") (class "Default")
      (node (ref "R1") (pin "1") (pinfunction "1_1") (pintype "passive"))
      (node (ref "R2") (pin "2") (pinfunction "2_2") (pintype "passive"))
    )
    (net (code "46") (name "Net-(R3-Pad1)") (class "Default")
      (node (ref "R3") (pin "1") (pinfunction "1_1") (pintype "passive"))
      (node (ref "R4") (pin "2") (pinfunction "2_2") (pintype "passive"))
    )
    (net (code "47") (name "Net-(R13-Pad1)") (class "Default")
      (node (ref "R13") (pin "1") (pinfunction "1_1") (pintype "passive"))
      (node (ref "R14") (pin "2") (pinfunction "2_2") (pintype "passive"))
    )
    (net (code "48") (name "Net-(R15-Pad1)") (class "Default")
      (node (ref "R15") (pin "1") (pinfunction "1_1") (pintype "passive"))
      (node (ref "R16") (pin "2") (pinfunction "2_2") (pintype "passive"))
    )
    (net (code "49") (name "Net-(U1-BOOT)") (class "Default")
      (node (ref "C1") (pin "2") (pinfunction "2_2") (pintype "passive"))
      (node (ref "U1") (pin "1") (pinfunction "BOOT_1") (pintype "passive"))
    )
    (net (code "50") (name "Net-(U1-VSENSE)") (class "Default")
      (node (ref "R5") (pin "1") (pinfunction "1_1") (pintype "passive"))
      (node (ref "R9") (pin "2") (pinfunction "2_2") (pintype "passive"))
      (node (ref "U1") (pin "4") (pinfunction "VSENSE_4") (pintype "input"))
    )
    (net (code "51") (name "Net-(U2A-1IN+)") (class "Default")
      (node (ref "D8") (pin "3") (pinfunction "3_3") (pintype "passive"))
      (node (ref "R16") (pin "1") (pinfunction "1_1") (pintype "passive"))
      (node (ref "R18") (pin "1") (pinfunction "1_1") (pintype "passive"))
      (node (ref "U2") (pin "3") (pinfunction "1IN+_3") (pintype "input"))
    )
    (net (code "52") (name "Net-(U2A-1IN-)") (class "Default")
      (node (ref "R22") (pin "2") (pinfunction "2_2") (pintype "passive"))
      (node (ref "U2") (pin "2") (pinfunction "1IN-_2") (pintype "input"))
    )
    (net (code "53") (name "Net-(U2A-1OUT)") (class "Default")
      (node (ref "R17") (pin "1") (pinfunction "1_1") (pintype "passive"))
      (node (ref "R20") (pin "1") (pinfunction "1_1") (pintype "passive"))
      (node (ref "R22") (pin "1") (pinfunction "1_1") (pintype "passive"))
      (node (ref "U2") (pin "1") (pinfunction "1OUT_1") (pintype "output"))
    )
    (net (code "54") (name "Net-(U2B-2IN+)") (class "Default")
      (node (ref "D4") (pin "3") (pinfunction "3_3") (pintype "passive"))
      (node (ref "R4") (pin "1") (pinfunction "1_1") (pintype "passive"))
      (node (ref "R7") (pin "1") (pinfunction "1_1") (pintype "passive"))
      (node (ref "U2") (pin "5") (pinfunction "2IN+_5") (pintype "input"))
    )
    (net (code "55") (name "Net-(U2B-2IN-)") (class "Default")
      (node (ref "R10") (pin "2") (pinfunction "2_2") (pintype "passive"))
      (node (ref "U2") (pin "6") (pinfunction "2IN-_6") (pintype "input"))
    )
    (net (code "56") (name "Net-(U2B-2OUT)") (class "Default")
      (node (ref "R10") (pin "1") (pinfunction "1_1") (pintype "passive"))
      (node (ref "R6") (pin "1") (pinfunction "1_1") (pintype "passive"))
      (node (ref "R8") (pin "1") (pinfunction "1_1") (pintype "passive"))
      (node (ref "U2") (pin "7") (pinfunction "2OUT_7") (pintype "output"))
    )
    (net (code "57") (name "Net-(U3-ISET)") (class "Default")
      (node (ref "R21") (pin "2") (pinfunction "2_2") (pintype "passive"))
      (node (ref "U3") (pin "3") (pinfunction "ISET_3") (pintype "passive"))
    )
    (net (code "58") (name "VCC") (class "Default")
      (node (ref "D2") (pin "2") (pinfunction "A_2") (pintype "passive"))
      (node (ref "J4") (pin "12") (pinfunction "12_12") (pintype "passive"))
    )
    (net (code "59") (name "VLIM") (class "Default")
      (node (ref "C10") (pin "1") (pinfunction "1_1") (pintype "passive"))
      (node (ref "C9") (pin "1") (pinfunction "1_1") (pintype "passive"))
      (node (ref "D9") (pin "1") (pinfunction "K_1") (pintype "passive"))
      (node (ref "J3") (pin "1") (pinfunction "1_1") (pintype "passive"))
      (node (ref "J3") (pin "2") (pinfunction "2_2") (pintype "passive"))
      (node (ref "Q2") (pin "3") (pinfunction "C_3") (pintype "passive"))
      (node (ref "U2") (pin "8") (pinfunction "VCC_8") (pintype "power_in"))
    )
    (net (code "60") (name "Vs_out") (class "Default")
      (node (ref "D3") (pin "2") (pinfunction "A_2") (pintype "passive"))
      (node (ref "D5") (pin "1") (pinfunction "K_1") (pintype "passive"))
      (node (ref "F1") (pin "2") (pinfunction "2_2") (pintype "passive"))
      (node (ref "J2") (pin "1") (pinfunction "1_1") (pintype "passive"))
      (node (ref "J2") (pin "2") (pinfunction "2_2") (pintype "passive"))
      (node (ref "Q2") (pin "2") (pinfunction "E_2") (pintype "passive"))
      (node (ref "R12") (pin "1") (pinfunction "1_1") (pintype "passive"))
    )
    (net (code "61") (name "unconnected-(M1-Pad1)") (class "Default")
      (node (ref "M1") (pin "1") (pinfunction "1_1") (pintype "passive"))
    )
    (net (code "62") (name "unconnected-(M2-Pad1)") (class "Default")
      (node (ref "M2") (pin "1") (pinfunction "1_1") (pintype "passive"))
    )
    (net (code "63") (name "unconnected-(U1-ENA-Pad5)") (class "Default")
      (node (ref "U1") (pin "5") (pinfunction "ENA_5") (pintype "input+no_connect"))
    )
    (net (code "64") (name "unconnected-(U1-NC-Pad2)") (class "Default")
      (node (ref "U1") (pin "2") (pinfunction "NC_2") (pintype "passive+no_connect"))
    )
    (net (code "65") (name "unconnected-(U1-NC-Pad3)") (class "Default")
      (node (ref "U1") (pin "3") (pinfunction "NC_3") (pintype "passive+no_connect"))
    )
  )
)
